# SparkFun_Mini_FET_Shield.net
KiCad netlist of a schematic drawn in EAGLE
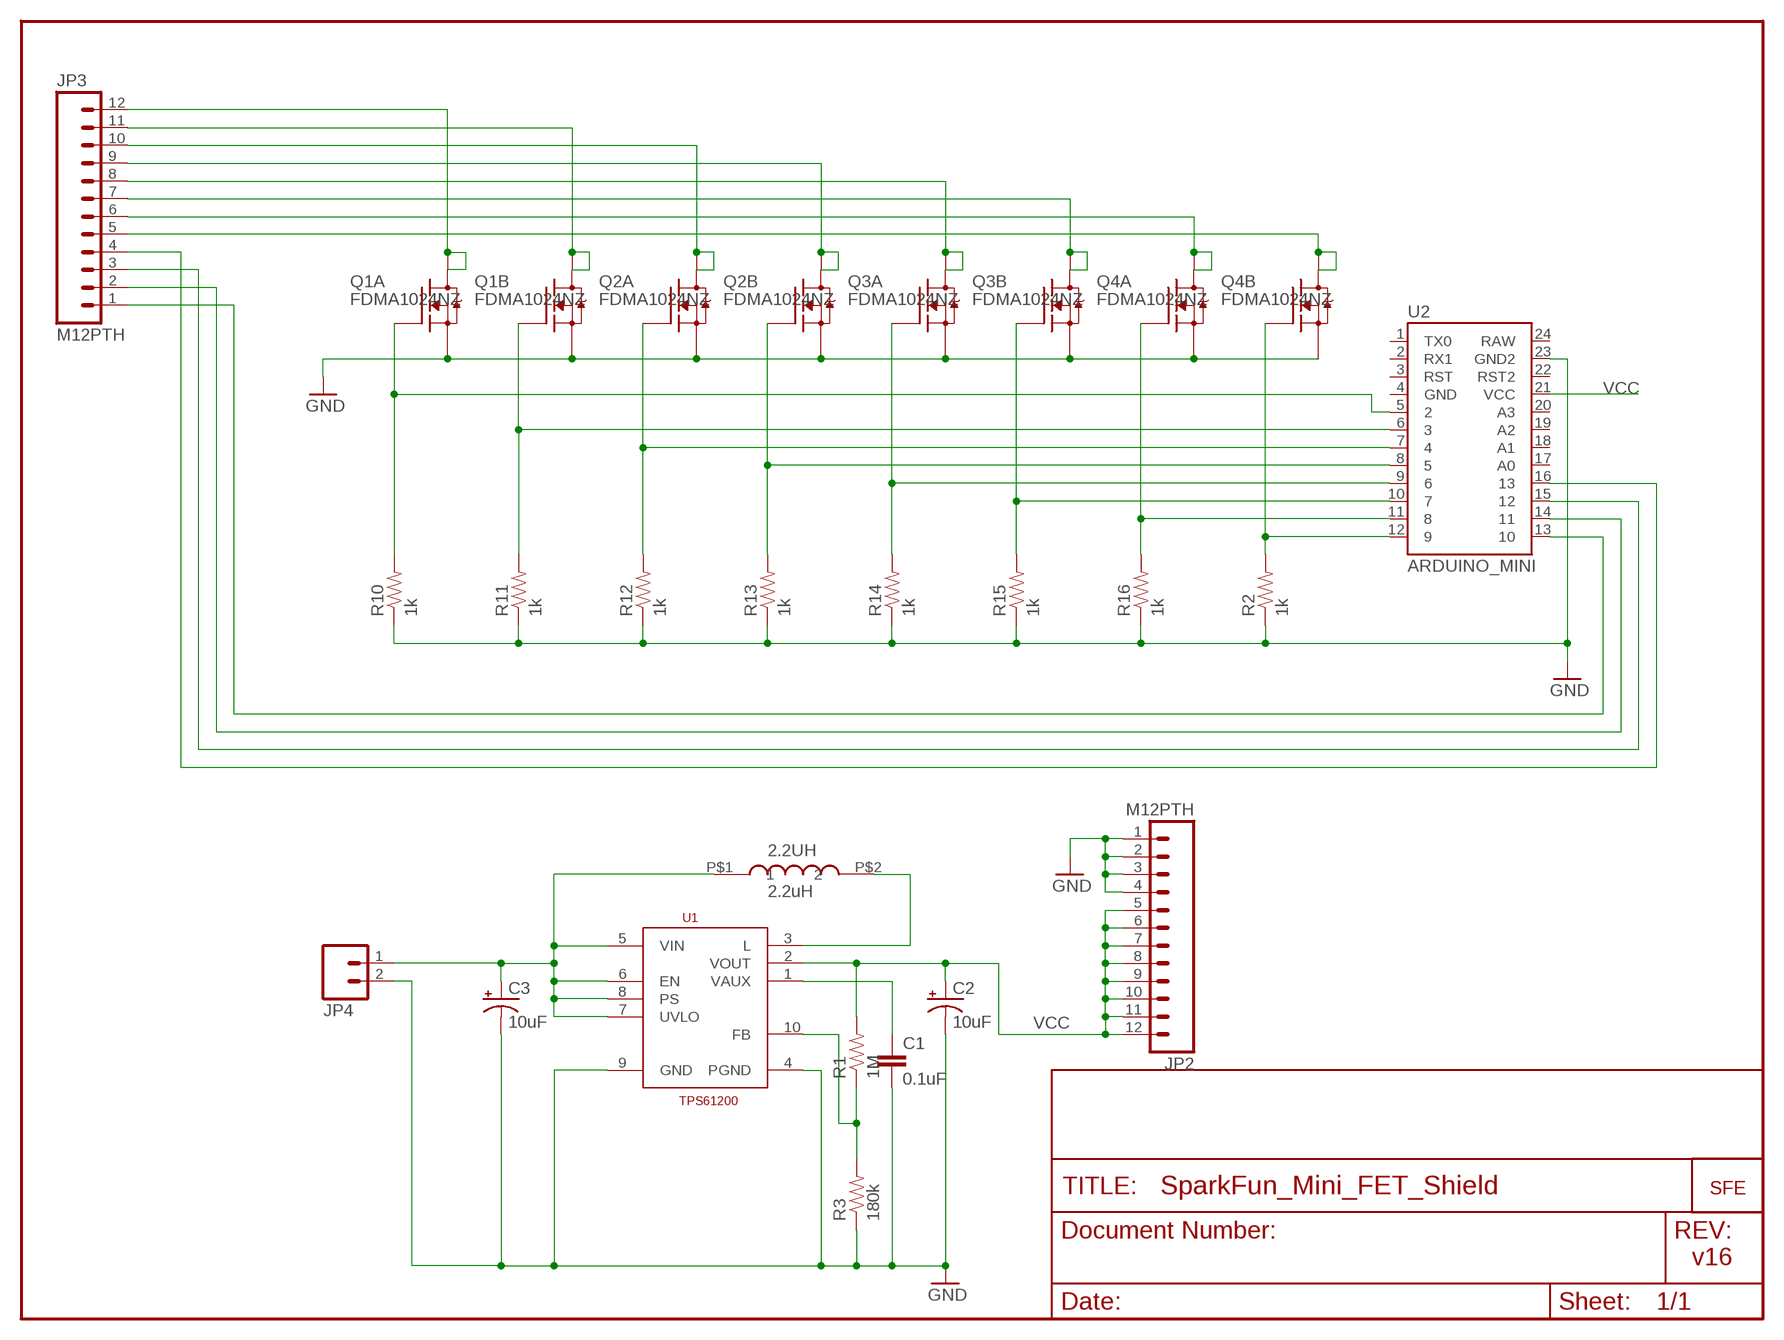
[diagram p0: schematic, sheet 1]

(export (version "E")
  (design (tool "Eeschema 10.0.6"))
  (components
    (comp (ref "2.2UH")
      (value "2.2uH")
      (footprint "eagle-import:VLF4012A")
      (libsource (lib "eagle-import") (part "VLF4012A"))
    )
    (comp (ref "C1")
      (value "0.1uF")
      (footprint "eagle-import:0402-CAP")
      (libsource (lib "eagle-import") (part "CAP0402-CAP"))
    )
    (comp (ref "C2")
      (value "10uF")
      (footprint "eagle-import:EIA3216")
      (libsource (lib "eagle-import") (part "CAP_POL1206"))
    )
    (comp (ref "C3")
      (value "10uF")
      (footprint "eagle-import:EIA3216")
      (libsource (lib "eagle-import") (part "CAP_POL1206"))
    )
    (comp (ref "JP2")
      (value "M12PTH")
      (footprint "eagle-import:1X12")
      (libsource (lib "eagle-import") (part "M12PTH"))
    )
    (comp (ref "JP3")
      (value "M12PTH")
      (footprint "eagle-import:1X12")
      (libsource (lib "eagle-import") (part "M12PTH"))
    )
    (comp (ref "JP4")
      (value "M02PTH")
      (footprint "eagle-import:1X02")
      (libsource (lib "eagle-import") (part "M02PTH"))
    )
    (comp (ref "JP5")
      (value "LOGO-SFESK")
      (footprint "eagle-import:SFE-LOGO-FLAME")
      (libsource (lib "eagle-import") (part "LOGO-SFESK"))
    )
    (comp (ref "Q1")
      (value "FDMA1024NZ")
      (footprint "eagle-import:MICROFET_2X2")
      (libsource (lib "eagle-import") (part "FDMA1024NZ"))
    )
    (comp (ref "Q2")
      (value "FDMA1024NZ")
      (footprint "eagle-import:MICROFET_2X2")
      (libsource (lib "eagle-import") (part "FDMA1024NZ"))
    )
    (comp (ref "Q3")
      (value "FDMA1024NZ")
      (footprint "eagle-import:MICROFET_2X2")
      (libsource (lib "eagle-import") (part "FDMA1024NZ"))
    )
    (comp (ref "Q4")
      (value "FDMA1024NZ")
      (footprint "eagle-import:MICROFET_2X2")
      (libsource (lib "eagle-import") (part "FDMA1024NZ"))
    )
    (comp (ref "R1")
      (value "1M")
      (footprint "eagle-import:0402-RES")
      (libsource (lib "eagle-import") (part "RESISTOR0402-RES"))
    )
    (comp (ref "R2")
      (value "1k")
      (footprint "eagle-import:0402-RES")
      (libsource (lib "eagle-import") (part "RESISTOR0402-RES"))
    )
    (comp (ref "R3")
      (value "180k")
      (footprint "eagle-import:0402-RES")
      (libsource (lib "eagle-import") (part "RESISTOR0402-RES"))
    )
    (comp (ref "R10")
      (value "1k")
      (footprint "eagle-import:0402-RES")
      (libsource (lib "eagle-import") (part "RESISTOR0402-RES"))
    )
    (comp (ref "R11")
      (value "1k")
      (footprint "eagle-import:0402-RES")
      (libsource (lib "eagle-import") (part "RESISTOR0402-RES"))
    )
    (comp (ref "R12")
      (value "1k")
      (footprint "eagle-import:0402-RES")
      (libsource (lib "eagle-import") (part "RESISTOR0402-RES"))
    )
    (comp (ref "R13")
      (value "1k")
      (footprint "eagle-import:0402-RES")
      (libsource (lib "eagle-import") (part "RESISTOR0402-RES"))
    )
    (comp (ref "R14")
      (value "1k")
      (footprint "eagle-import:0402-RES")
      (libsource (lib "eagle-import") (part "RESISTOR0402-RES"))
    )
    (comp (ref "R15")
      (value "1k")
      (footprint "eagle-import:0402-RES")
      (libsource (lib "eagle-import") (part "RESISTOR0402-RES"))
    )
    (comp (ref "R16")
      (value "1k")
      (footprint "eagle-import:0402-RES")
      (libsource (lib "eagle-import") (part "RESISTOR0402-RES"))
    )
    (comp (ref "U1")
      (value "TPS61200")
      (footprint "eagle-import:DRC-S-PVSON-N10")
      (libsource (lib "eagle-import") (part "TPS61200"))
    )
    (comp (ref "U2")
      (value "ARDUINO_MINI")
      (footprint "eagle-import:ARDUINO_MINI")
      (libsource (lib "eagle-import") (part "ARDUINO_MINI"))
    )
  )
  (nets
    (net (code "1") (name "/VCC") (class "Default")
      (node (ref "C2") (pin "A") (pinfunction "+_A") (pintype "passive"))
      (node (ref "JP2") (pin "10") (pinfunction "10_10") (pintype "passive"))
      (node (ref "JP2") (pin "11") (pinfunction "11_11") (pintype "passive"))
      (node (ref "JP2") (pin "12") (pinfunction "12_12") (pintype "passive"))
      (node (ref "JP2") (pin "5") (pinfunction "5_5") (pintype "passive"))
      (node (ref "JP2") (pin "6") (pinfunction "6_6") (pintype "passive"))
      (node (ref "JP2") (pin "7") (pinfunction "7_7") (pintype "passive"))
      (node (ref "JP2") (pin "8") (pinfunction "8_8") (pintype "passive"))
      (node (ref "JP2") (pin "9") (pinfunction "9_9") (pintype "passive"))
      (node (ref "R1") (pin "2") (pinfunction "2_2") (pintype "passive"))
      (node (ref "U1") (pin "2") (pinfunction "VOUT_2") (pintype "bidirectional"))
      (node (ref "U2") (pin "21") (pinfunction "VCC_21") (pintype "bidirectional"))
    )
    (net (code "2") (name "GND") (class "Default")
      (node (ref "C1") (pin "2") (pinfunction "2_2") (pintype "passive"))
      (node (ref "C2") (pin "C") (pinfunction "-_C") (pintype "passive"))
      (node (ref "C3") (pin "C") (pinfunction "-_C") (pintype "passive"))
      (node (ref "JP2") (pin "1") (pinfunction "1_1") (pintype "passive"))
      (node (ref "JP2") (pin "2") (pinfunction "2_2") (pintype "passive"))
      (node (ref "JP2") (pin "3") (pinfunction "3_3") (pintype "passive"))
      (node (ref "JP2") (pin "4") (pinfunction "4_4") (pintype "passive"))
      (node (ref "JP4") (pin "2") (pinfunction "2_2") (pintype "passive"))
      (node (ref "Q1") (pin "S1") (pinfunction "S_S1") (pintype "passive"))
      (node (ref "Q1") (pin "S2") (pinfunction "S_S2") (pintype "passive"))
      (node (ref "Q2") (pin "S1") (pinfunction "S_S1") (pintype "passive"))
      (node (ref "Q2") (pin "S2") (pinfunction "S_S2") (pintype "passive"))
      (node (ref "Q3") (pin "S1") (pinfunction "S_S1") (pintype "passive"))
      (node (ref "Q3") (pin "S2") (pinfunction "S_S2") (pintype "passive"))
      (node (ref "Q4") (pin "S1") (pinfunction "S_S1") (pintype "passive"))
      (node (ref "Q4") (pin "S2") (pinfunction "S_S2") (pintype "passive"))
      (node (ref "R10") (pin "1") (pinfunction "1_1") (pintype "passive"))
      (node (ref "R11") (pin "1") (pinfunction "1_1") (pintype "passive"))
      (node (ref "R12") (pin "1") (pinfunction "1_1") (pintype "passive"))
      (node (ref "R13") (pin "1") (pinfunction "1_1") (pintype "passive"))
      (node (ref "R14") (pin "1") (pinfunction "1_1") (pintype "passive"))
      (node (ref "R15") (pin "1") (pinfunction "1_1") (pintype "passive"))
      (node (ref "R16") (pin "1") (pinfunction "1_1") (pintype "passive"))
      (node (ref "R2") (pin "1") (pinfunction "1_1") (pintype "passive"))
      (node (ref "R3") (pin "1") (pinfunction "1_1") (pintype "passive"))
      (node (ref "U1") (pin "4") (pinfunction "PGND_4") (pintype "bidirectional"))
      (node (ref "U1") (pin "9") (pinfunction "GND_9") (pintype "bidirectional"))
      (node (ref "U2") (pin "23") (pinfunction "GND2_23") (pintype "bidirectional"))
    )
    (net (code "3") (name "Net-(2.2UH-1)") (class "Default")
      (node (ref "2.2UH") (pin "P$1") (pinfunction "1_P$1") (pintype "bidirectional"))
      (node (ref "C3") (pin "A") (pinfunction "+_A") (pintype "passive"))
      (node (ref "JP4") (pin "1") (pinfunction "1_1") (pintype "passive"))
      (node (ref "U1") (pin "5") (pinfunction "VIN_5") (pintype "bidirectional"))
      (node (ref "U1") (pin "6") (pinfunction "EN_6") (pintype "bidirectional"))
      (node (ref "U1") (pin "7") (pinfunction "UVLO_7") (pintype "bidirectional"))
      (node (ref "U1") (pin "8") (pinfunction "PS_8") (pintype "bidirectional"))
    )
    (net (code "4") (name "Net-(2.2UH-2)") (class "Default")
      (node (ref "2.2UH") (pin "P$2") (pinfunction "2_P$2") (pintype "bidirectional"))
      (node (ref "U1") (pin "3") (pinfunction "L_3") (pintype "bidirectional"))
    )
    (net (code "5") (name "Net-(Q1A-D)") (class "Default")
      (node (ref "JP3") (pin "12") (pinfunction "12_12") (pintype "passive"))
      (node (ref "Q1") (pin "D1") (pinfunction "D_D1") (pintype "passive"))
      (node (ref "Q1") (pin "D1_2") (pinfunction "D1_D1_2") (pintype "passive"))
    )
    (net (code "6") (name "Net-(Q1A-G)") (class "Default")
      (node (ref "Q1") (pin "G1") (pinfunction "G_G1") (pintype "passive"))
      (node (ref "R10") (pin "2") (pinfunction "2_2") (pintype "passive"))
      (node (ref "U2") (pin "5") (pinfunction "2_5") (pintype "bidirectional"))
    )
    (net (code "7") (name "Net-(Q1B-D)") (class "Default")
      (node (ref "JP3") (pin "11") (pinfunction "11_11") (pintype "passive"))
      (node (ref "Q1") (pin "D2") (pinfunction "D_D2") (pintype "passive"))
      (node (ref "Q1") (pin "D2_2") (pinfunction "D1_D2_2") (pintype "passive"))
    )
    (net (code "8") (name "Net-(Q1B-G)") (class "Default")
      (node (ref "Q1") (pin "G2") (pinfunction "G_G2") (pintype "passive"))
      (node (ref "R11") (pin "2") (pinfunction "2_2") (pintype "passive"))
      (node (ref "U2") (pin "6") (pinfunction "3_6") (pintype "bidirectional"))
    )
    (net (code "9") (name "Net-(Q2A-D)") (class "Default")
      (node (ref "JP3") (pin "10") (pinfunction "10_10") (pintype "passive"))
      (node (ref "Q2") (pin "D1") (pinfunction "D_D1") (pintype "passive"))
      (node (ref "Q2") (pin "D1_2") (pinfunction "D1_D1_2") (pintype "passive"))
    )
    (net (code "10") (name "Net-(Q2A-G)") (class "Default")
      (node (ref "Q2") (pin "G1") (pinfunction "G_G1") (pintype "passive"))
      (node (ref "R12") (pin "2") (pinfunction "2_2") (pintype "passive"))
      (node (ref "U2") (pin "7") (pinfunction "4_7") (pintype "bidirectional"))
    )
    (net (code "11") (name "Net-(Q2B-D)") (class "Default")
      (node (ref "JP3") (pin "9") (pinfunction "9_9") (pintype "passive"))
      (node (ref "Q2") (pin "D2") (pinfunction "D_D2") (pintype "passive"))
      (node (ref "Q2") (pin "D2_2") (pinfunction "D1_D2_2") (pintype "passive"))
    )
    (net (code "12") (name "Net-(Q2B-G)") (class "Default")
      (node (ref "Q2") (pin "G2") (pinfunction "G_G2") (pintype "passive"))
      (node (ref "R13") (pin "2") (pinfunction "2_2") (pintype "passive"))
      (node (ref "U2") (pin "8") (pinfunction "5_8") (pintype "bidirectional"))
    )
    (net (code "13") (name "Net-(Q3A-D)") (class "Default")
      (node (ref "JP3") (pin "8") (pinfunction "8_8") (pintype "passive"))
      (node (ref "Q3") (pin "D1") (pinfunction "D_D1") (pintype "passive"))
      (node (ref "Q3") (pin "D1_2") (pinfunction "D1_D1_2") (pintype "passive"))
    )
    (net (code "14") (name "Net-(Q3A-G)") (class "Default")
      (node (ref "Q3") (pin "G1") (pinfunction "G_G1") (pintype "passive"))
      (node (ref "R14") (pin "2") (pinfunction "2_2") (pintype "passive"))
      (node (ref "U2") (pin "9") (pinfunction "6_9") (pintype "bidirectional"))
    )
    (net (code "15") (name "Net-(Q3B-D)") (class "Default")
      (node (ref "JP3") (pin "7") (pinfunction "7_7") (pintype "passive"))
      (node (ref "Q3") (pin "D2") (pinfunction "D_D2") (pintype "passive"))
      (node (ref "Q3") (pin "D2_2") (pinfunction "D1_D2_2") (pintype "passive"))
    )
    (net (code "16") (name "Net-(Q3B-G)") (class "Default")
      (node (ref "Q3") (pin "G2") (pinfunction "G_G2") (pintype "passive"))
      (node (ref "R15") (pin "2") (pinfunction "2_2") (pintype "passive"))
      (node (ref "U2") (pin "10") (pinfunction "7_10") (pintype "bidirectional"))
    )
    (net (code "17") (name "Net-(Q4A-D)") (class "Default")
      (node (ref "JP3") (pin "6") (pinfunction "6_6") (pintype "passive"))
      (node (ref "Q4") (pin "D1") (pinfunction "D_D1") (pintype "passive"))
      (node (ref "Q4") (pin "D1_2") (pinfunction "D1_D1_2") (pintype "passive"))
    )
    (net (code "18") (name "Net-(Q4A-G)") (class "Default")
      (node (ref "Q4") (pin "G1") (pinfunction "G_G1") (pintype "passive"))
      (node (ref "R16") (pin "2") (pinfunction "2_2") (pintype "passive"))
      (node (ref "U2") (pin "11") (pinfunction "8_11") (pintype "bidirectional"))
    )
    (net (code "19") (name "Net-(Q4B-D)") (class "Default")
      (node (ref "JP3") (pin "5") (pinfunction "5_5") (pintype "passive"))
      (node (ref "Q4") (pin "D2") (pinfunction "D_D2") (pintype "passive"))
      (node (ref "Q4") (pin "D2_2") (pinfunction "D1_D2_2") (pintype "passive"))
    )
    (net (code "20") (name "Net-(Q4B-G)") (class "Default")
      (node (ref "Q4") (pin "G2") (pinfunction "G_G2") (pintype "passive"))
      (node (ref "R2") (pin "2") (pinfunction "2_2") (pintype "passive"))
      (node (ref "U2") (pin "12") (pinfunction "9_12") (pintype "bidirectional"))
    )
    (net (code "21") (name "Net-(U1-FB)") (class "Default")
      (node (ref "R1") (pin "1") (pinfunction "1_1") (pintype "passive"))
      (node (ref "R3") (pin "2") (pinfunction "2_2") (pintype "passive"))
      (node (ref "U1") (pin "10") (pinfunction "FB_10") (pintype "bidirectional"))
    )
    (net (code "22") (name "Net-(U1-VAUX)") (class "Default")
      (node (ref "C1") (pin "1") (pinfunction "1_1") (pintype "passive"))
      (node (ref "U1") (pin "1") (pinfunction "VAUX_1") (pintype "bidirectional"))
    )
    (net (code "23") (name "Net-(U2-10)") (class "Default")
      (node (ref "JP3") (pin "1") (pinfunction "1_1") (pintype "passive"))
      (node (ref "U2") (pin "13") (pinfunction "10_13") (pintype "bidirectional"))
    )
    (net (code "24") (name "Net-(U2-11)") (class "Default")
      (node (ref "JP3") (pin "2") (pinfunction "2_2") (pintype "passive"))
      (node (ref "U2") (pin "14") (pinfunction "11_14") (pintype "bidirectional"))
    )
    (net (code "25") (name "Net-(U2-12)") (class "Default")
      (node (ref "JP3") (pin "3") (pinfunction "3_3") (pintype "passive"))
      (node (ref "U2") (pin "15") (pinfunction "12_15") (pintype "bidirectional"))
    )
    (net (code "26") (name "Net-(U2-13)") (class "Default")
      (node (ref "JP3") (pin "4") (pinfunction "4_4") (pintype "passive"))
      (node (ref "U2") (pin "16") (pinfunction "13_16") (pintype "bidirectional"))
    )
    (net (code "27") (name "unconnected-(U2-A0-Pad17)") (class "Default")
      (node (ref "U2") (pin "17") (pinfunction "A0_17") (pintype "bidirectional"))
    )
    (net (code "28") (name "unconnected-(U2-A1-Pad18)") (class "Default")
      (node (ref "U2") (pin "18") (pinfunction "A1_18") (pintype "bidirectional"))
    )
    (net (code "29") (name "unconnected-(U2-A2-Pad19)") (class "Default")
      (node (ref "U2") (pin "19") (pinfunction "A2_19") (pintype "bidirectional"))
    )
    (net (code "30") (name "unconnected-(U2-A3-Pad20)") (class "Default")
      (node (ref "U2") (pin "20") (pinfunction "A3_20") (pintype "bidirectional"))
    )
    (net (code "31") (name "unconnected-(U2-GND-Pad4)") (class "Default")
      (node (ref "U2") (pin "4") (pinfunction "GND_4") (pintype "bidirectional"))
    )
    (net (code "32") (name "unconnected-(U2-RAW-Pad24)") (class "Default")
      (node (ref "U2") (pin "24") (pinfunction "RAW_24") (pintype "bidirectional"))
    )
    (net (code "33") (name "unconnected-(U2-RST-Pad3)") (class "Default")
      (node (ref "U2") (pin "3") (pinfunction "RST_3") (pintype "bidirectional"))
    )
    (net (code "34") (name "unconnected-(U2-RST2-Pad22)") (class "Default")
      (node (ref "U2") (pin "22") (pinfunction "RST2_22") (pintype "bidirectional"))
    )
    (net (code "35") (name "unconnected-(U2-RX1-Pad2)") (class "Default")
      (node (ref "U2") (pin "2") (pinfunction "RX1_2") (pintype "bidirectional"))
    )
    (net (code "36") (name "unconnected-(U2-TX0-Pad1)") (class "Default")
      (node (ref "U2") (pin "1") (pinfunction "TX0_1") (pintype "bidirectional"))
    )
  )
)
